# Flash_Memory.net
KiCad netlist of a schematic drawn in Altium Designer
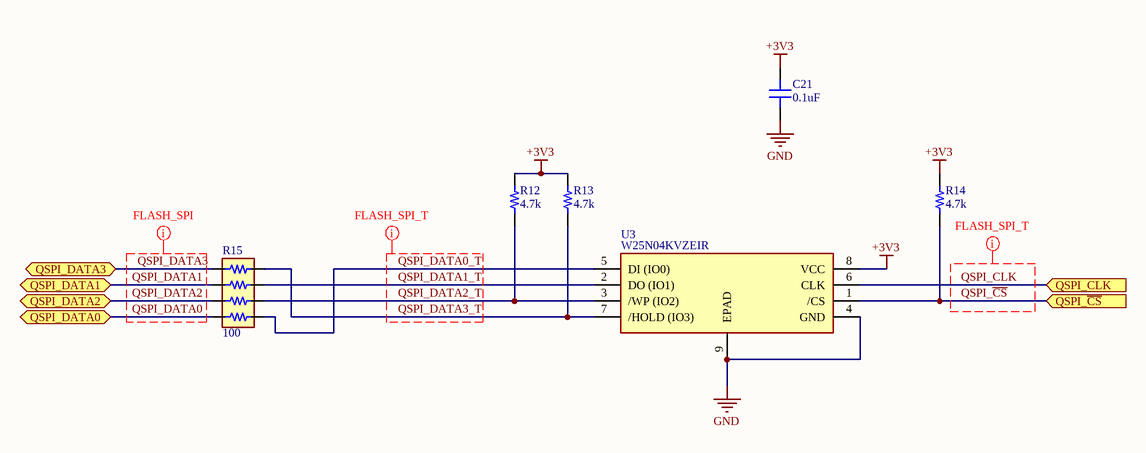
[diagram p0: Flash_Memory.SchDoc]

(export (version "E")
  (design (tool "Eeschema 10.0.6"))
  (components
    (comp (ref "C21")
      (value "0.1uF")
      (footprint "CAP0402")
      (description "CAP CER 0.1uF 16V X7R 0402 10%")
      (fields (field (name "TOLERANCE") "10%") (field (name "VOLTAGE") "16V"))
      (libsource (lib "Pasivos") (part "C0402C104K4RAC"))
    )
    (comp (ref "R12")
      (value "4.7k")
      (footprint "RES0402")
      (description "RES SMD 4.7K OHM 1% 0.063W 0402")
      (fields (field (name "POWER") "0.063 W") (field (name "MANUFACTURER") "Vishay"))
      (libsource (lib "Pasivos") (part "CRCW04024K70FK"))
    )
    (comp (ref "R13")
      (value "4.7k")
      (footprint "RES0402")
      (description "RES SMD 4.7K OHM 1% 0.063W 0402")
      (fields (field (name "POWER") "0.063 W") (field (name "MANUFACTURER") "Vishay"))
      (libsource (lib "Pasivos") (part "CRCW04024K70FK"))
    )
    (comp (ref "R14")
      (value "4.7k")
      (footprint "RES0402")
      (description "RES SMD 4.7K OHM 1% 0.063W 0402")
      (fields (field (name "POWER") "0.063 W") (field (name "MANUFACTURER") "Vishay"))
      (libsource (lib "Pasivos") (part "CRCW04024K70FK"))
    )
    (comp (ref "R15")
      (value "100")
      (footprint "ArrayResistor-1206")
      (description "RES ARRAY 4 RES 100 OHM 1206")
      (libsource (lib "Pasivos") (part "EXB-38V101JV"))
    )
    (comp (ref "U3")
      (value "W25N04KVZEIR")
      (footprint "WSON-8")
      (description "QSPINAND 4G-BIT FLASH MEMORY WITH DUAL/QUAD SPI BUFFER READ & SEQUENTIAL READ")
      (libsource (lib "Integrated_Circuits") (part "W25N04KVZEIR"))
    )
  )
  (nets
    (net (code "1") (name "+3V3") (class "Default")
      (node (ref "C21") (pin "2") (pinfunction "2_2") (pintype "passive"))
      (node (ref "R12") (pin "2") (pinfunction "2_2") (pintype "passive"))
      (node (ref "R13") (pin "2") (pinfunction "2_2") (pintype "passive"))
      (node (ref "R14") (pin "2") (pinfunction "2_2") (pintype "passive"))
      (node (ref "U3") (pin "8") (pinfunction "VCC_8") (pintype "power_in"))
    )
    (net (code "2") (name "/QSPI_CLK") (class "Default")
      (node (ref "U3") (pin "6") (pinfunction "CLK_6") (pintype "passive"))
    )
    (net (code "3") (name "/QSPI_DATA0") (class "Default")
      (node (ref "R15") (pin "4") (pinfunction "4_4") (pintype "passive"))
    )
    (net (code "4") (name "/QSPI_DATA0_T") (class "Default")
      (node (ref "R15") (pin "5") (pinfunction "5_5") (pintype "passive"))
      (node (ref "U3") (pin "5") (pinfunction "DI_(IO0)_5") (pintype "passive"))
    )
    (net (code "5") (name "/QSPI_DATA1") (class "Default")
      (node (ref "R15") (pin "2") (pinfunction "2_2") (pintype "passive"))
    )
    (net (code "6") (name "/QSPI_DATA1_T") (class "Default")
      (node (ref "R15") (pin "7") (pinfunction "7_7") (pintype "passive"))
      (node (ref "U3") (pin "2") (pinfunction "DO_(IO1)_2") (pintype "passive"))
    )
    (net (code "7") (name "/QSPI_DATA2") (class "Default")
      (node (ref "R15") (pin "3") (pinfunction "3_3") (pintype "passive"))
    )
    (net (code "8") (name "/QSPI_DATA2_T") (class "Default")
      (node (ref "R12") (pin "1") (pinfunction "1_1") (pintype "passive"))
      (node (ref "R15") (pin "6") (pinfunction "6_6") (pintype "passive"))
      (node (ref "U3") (pin "3") (pinfunction "/WP_(IO2)_3") (pintype "passive"))
    )
    (net (code "9") (name "/QSPI_DATA3") (class "Default")
      (node (ref "R15") (pin "1") (pinfunction "1_1") (pintype "passive"))
    )
    (net (code "10") (name "/QSPI_DATA3_T") (class "Default")
      (node (ref "R13") (pin "1") (pinfunction "1_1") (pintype "passive"))
      (node (ref "R15") (pin "8") (pinfunction "8_8") (pintype "passive"))
      (node (ref "U3") (pin "7") (pinfunction "/HOLD_(IO3)_7") (pintype "passive"))
    )
    (net (code "11") (name "/QSPI_~{CS}") (class "Default")
      (node (ref "R14") (pin "1") (pinfunction "1_1") (pintype "passive"))
      (node (ref "U3") (pin "1") (pinfunction "/CS_1") (pintype "passive"))
    )
    (net (code "12") (name "GND") (class "Default")
      (node (ref "C21") (pin "1") (pinfunction "1_1") (pintype "passive"))
      (node (ref "U3") (pin "4") (pinfunction "GND_4") (pintype "power_in"))
      (node (ref "U3") (pin "9") (pinfunction "EPAD_9") (pintype "passive"))
    )
  )
)
